# US_SB_Orinet.net
KiCad netlist of a schematic drawn in Altium Designer
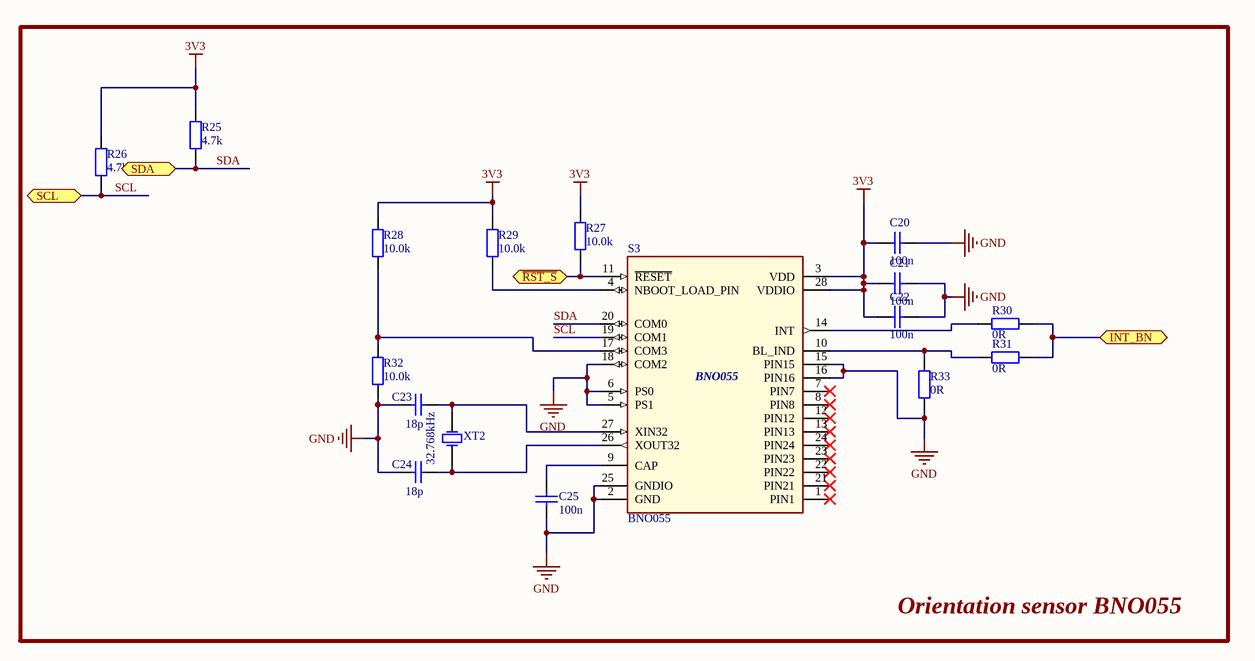
[diagram p0: US_SB_Orinet.SchDoc]

(export (version "E")
  (design (tool "Eeschema 10.0.6"))
  (components
    (comp (ref "C20")
      (value "100n")
      (footprint "C0603_IPC_HD")
      (description "CAP CER 0.1UF 16V X7R 0603")
      (fields
        (field (name "MANUFACTURER") "Samsung Electro-Mechanics")
        (field (name "MANUFACTURER PART NUMBER") "CL10B104KO8NNNC")
      )
      (libsource (lib "alfasat_parts_lib") (part "CL10B104KO8NNNC"))
    )
    (comp (ref "C21")
      (value "100n")
      (footprint "C0603_IPC_HD")
      (description "CAP CER 0.1UF 16V X7R 0603")
      (fields
        (field (name "MANUFACTURER") "Samsung Electro-Mechanics")
        (field (name "MANUFACTURER PART NUMBER") "CL10B104KO8NNNC")
      )
      (libsource (lib "alfasat_parts_lib") (part "CL10B104KO8NNNC"))
    )
    (comp (ref "C22")
      (value "100n")
      (footprint "C0603_IPC_HD")
      (description "CAP CER 0.1UF 16V X7R 0603")
      (fields
        (field (name "MANUFACTURER") "Samsung Electro-Mechanics")
        (field (name "MANUFACTURER PART NUMBER") "CL10B104KO8NNNC")
      )
      (libsource (lib "alfasat_parts_lib") (part "CL10B104KO8NNNC"))
    )
    (comp (ref "C23")
      (value "18p")
      (footprint "C0603_IPC_HD")
      (description "CAP CER 18PF 50V C0G/NP0 0603")
      (fields
        (field (name "MANUFACTURER") "Samsung Electro-Mechanics")
        (field (name "MANUFACTURER PART NUMBER") "CL10C180JB8NNNC")
      )
      (libsource (lib "alfasat_lib") (part "CL10C180JB8NNNC"))
    )
    (comp (ref "C24")
      (value "18p")
      (footprint "C0603_IPC_HD")
      (description "CAP CER 18PF 50V C0G/NP0 0603")
      (fields
        (field (name "MANUFACTURER") "Samsung Electro-Mechanics")
        (field (name "MANUFACTURER PART NUMBER") "CL10C180JB8NNNC")
      )
      (libsource (lib "alfasat_lib") (part "CL10C180JB8NNNC"))
    )
    (comp (ref "C25")
      (value "100n")
      (footprint "C0603_IPC_HD")
      (description "CAP CER 0.1UF 16V X7R 0603")
      (fields
        (field (name "MANUFACTURER") "Samsung Electro-Mechanics")
        (field (name "MANUFACTURER PART NUMBER") "CL10B104KO8NNNC")
      )
      (libsource (lib "alfasat_parts_lib") (part "CL10B104KO8NNNC"))
    )
    (comp (ref "R25")
      (value "4.7k")
      (footprint "R0603_IPC_HD")
      (description "RES SMD 4.7K OHM 5% 1/10W 0603")
      (fields
        (field (name "MANUFACTURER") "Bourns Inc.")
        (field (name "MANUFACTURER PART NUMBER") "CR0603-JW-472ELF")
      )
      (libsource (lib "alfasat_lib_eps") (part "CR0603-JW-4.7k"))
    )
    (comp (ref "R26")
      (value "4.7k")
      (footprint "R0603_IPC_HD")
      (description "RES SMD 4.7K OHM 5% 1/10W 0603")
      (fields
        (field (name "MANUFACTURER") "Bourns Inc.")
        (field (name "MANUFACTURER PART NUMBER") "CR0603-JW-472ELF")
      )
      (libsource (lib "alfasat_lib_eps") (part "CR0603-JW-4.7k"))
    )
    (comp (ref "R27")
      (value "10.0k")
      (footprint "R0603_IPC_MD")
      (description "RES 10K OHM 1% 1/10W 0603")
      (fields
        (field (name "MANUFACTURER") "Stackpole Electronics Inc")
        (field (name "MANUFACTURER PART NUMBER") "RMCF0603FT10K0")
      )
      (libsource (lib "alfasat_parts_lib") (part "RMCF0603FT10K0"))
    )
    (comp (ref "R28")
      (value "10.0k")
      (footprint "R0603_IPC_MD")
      (description "RES 10K OHM 1% 1/10W 0603")
      (fields
        (field (name "MANUFACTURER") "Stackpole Electronics Inc")
        (field (name "MANUFACTURER PART NUMBER") "RMCF0603FT10K0")
      )
      (libsource (lib "alfasat_parts_lib") (part "RMCF0603FT10K0"))
    )
    (comp (ref "R29")
      (value "10.0k")
      (footprint "R0603_IPC_MD")
      (description "RES 10K OHM 1% 1/10W 0603")
      (fields
        (field (name "MANUFACTURER") "Stackpole Electronics Inc")
        (field (name "MANUFACTURER PART NUMBER") "RMCF0603FT10K0")
      )
      (libsource (lib "alfasat_parts_lib") (part "RMCF0603FT10K0"))
    )
    (comp (ref "R30")
      (value "0R")
      (footprint "R0603_IPC_MD")
      (description "RES SMD 0 OHM JUMPER 1/10W 0603")
      (fields
        (field (name "MANUFACTURER") "Bourns Inc.")
        (field (name "MANUFACTURER PART NUMBER") "CR0603-J/-000ELF")
      )
      (libsource (lib "") (part "CR0603-J/-000ELF_1"))
    )
    (comp (ref "R31")
      (value "0R")
      (footprint "R0603_IPC_MD")
      (description "RES SMD 0 OHM JUMPER 1/10W 0603")
      (fields
        (field (name "MANUFACTURER") "Bourns Inc.")
        (field (name "MANUFACTURER PART NUMBER") "CR0603-J/-000ELF")
      )
      (libsource (lib "") (part "CR0603-J/-000ELF_1"))
    )
    (comp (ref "R32")
      (value "10.0k")
      (footprint "R0603_IPC_MD")
      (description "RES 10K OHM 1% 1/10W 0603")
      (fields
        (field (name "MANUFACTURER") "Stackpole Electronics Inc")
        (field (name "MANUFACTURER PART NUMBER") "RMCF0603FT10K0")
      )
      (libsource (lib "alfasat_parts_lib") (part "RMCF0603FT10K0"))
    )
    (comp (ref "R33")
      (value "0R")
      (footprint "R0603_IPC_MD")
      (description "RES SMD 0 OHM JUMPER 1/10W 0603")
      (fields
        (field (name "MANUFACTURER") "Bourns Inc.")
        (field (name "MANUFACTURER PART NUMBER") "CR0603-J/-000ELF")
      )
      (libsource (lib "alfasat_lib") (part "CR0603-J/-000ELF"))
    )
    (comp (ref "S3")
      (value "BNO055")
      (footprint "BNO055_LGA28R50P4X10_380X520X100")
      (description "Accelerometer, Gyroscope, Magnetometer, 3 Axis Sensor I²C, UART Output")
      (fields (field (name "MANUFACTURER") "Bosch Sensortec"))
      (libsource (lib "alfasat_lib_eps") (part "BNO055"))
    )
    (comp (ref "XT2")
      (value "32.768kHz")
      (footprint "FC-135R")
      (description "32.768kHz ±20ppm Crystal 12.5pF 70 kOhms 2-SMD, No Lead")
      (fields
        (field (name "MANUFACTURER") "EPSON")
        (field (name "MANUFACTURER PART NUMBER") "FC-135 32.7680KA-A5")
      )
      (libsource (lib "alfasat_lib_eps") (part "FC-135-32.7680K"))
    )
  )
  (nets
    (net (code "1") (name "/INT_BN") (class "Default")
      (node (ref "R30") (pin "1") (pinfunction "1_1") (pintype "passive"))
      (node (ref "R31") (pin "1") (pinfunction "1_1") (pintype "passive"))
    )
    (net (code "2") (name "/SCL") (class "Default")
      (node (ref "R26") (pin "1") (pinfunction "1_1") (pintype "passive"))
      (node (ref "S3") (pin "19") (pinfunction "COM1_19") (pintype "bidirectional"))
    )
    (net (code "3") (name "/SDA") (class "Default")
      (node (ref "R25") (pin "1") (pinfunction "1_1") (pintype "passive"))
      (node (ref "S3") (pin "20") (pinfunction "COM0_20") (pintype "bidirectional"))
    )
    (net (code "4") (name "/~{RST_S}") (class "Default")
      (node (ref "R27") (pin "1") (pinfunction "1_1") (pintype "passive"))
      (node (ref "S3") (pin "11") (pinfunction "~{RESET}_11") (pintype "input"))
    )
    (net (code "5") (name "3V3") (class "Default")
      (node (ref "C20") (pin "1") (pinfunction "1_1") (pintype "passive"))
      (node (ref "C21") (pin "1") (pinfunction "1_1") (pintype "passive"))
      (node (ref "C22") (pin "1") (pinfunction "1_1") (pintype "passive"))
      (node (ref "R25") (pin "2") (pinfunction "2_2") (pintype "passive"))
      (node (ref "R26") (pin "2") (pinfunction "2_2") (pintype "passive"))
      (node (ref "R27") (pin "2") (pinfunction "2_2") (pintype "passive"))
      (node (ref "R28") (pin "2") (pinfunction "2_2") (pintype "passive"))
      (node (ref "R29") (pin "2") (pinfunction "2_2") (pintype "passive"))
      (node (ref "S3") (pin "28") (pinfunction "VDDIO_28") (pintype "passive"))
      (node (ref "S3") (pin "3") (pinfunction "VDD_3") (pintype "passive"))
    )
    (net (code "6") (name "GND") (class "Default")
      (node (ref "C20") (pin "2") (pinfunction "2_2") (pintype "passive"))
      (node (ref "C21") (pin "2") (pinfunction "2_2") (pintype "passive"))
      (node (ref "C22") (pin "2") (pinfunction "2_2") (pintype "passive"))
      (node (ref "C23") (pin "1") (pinfunction "1_1") (pintype "passive"))
      (node (ref "C24") (pin "1") (pinfunction "1_1") (pintype "passive"))
      (node (ref "C25") (pin "1") (pinfunction "1_1") (pintype "passive"))
      (node (ref "R32") (pin "1") (pinfunction "1_1") (pintype "passive"))
      (node (ref "R33") (pin "1") (pinfunction "1_1") (pintype "passive"))
      (node (ref "S3") (pin "15") (pinfunction "PIN15_15") (pintype "passive"))
      (node (ref "S3") (pin "16") (pinfunction "PIN16_16") (pintype "passive"))
      (node (ref "S3") (pin "18") (pinfunction "COM2_18") (pintype "bidirectional"))
      (node (ref "S3") (pin "2") (pinfunction "GND_2") (pintype "passive"))
      (node (ref "S3") (pin "25") (pinfunction "GNDIO_25") (pintype "passive"))
      (node (ref "S3") (pin "5") (pinfunction "PS1_5") (pintype "input"))
      (node (ref "S3") (pin "6") (pinfunction "PS0_6") (pintype "input"))
    )
    (net (code "7") (name "Net-(S3-BL_IND)") (class "Default")
      (node (ref "R31") (pin "2") (pinfunction "2_2") (pintype "passive"))
      (node (ref "R33") (pin "2") (pinfunction "2_2") (pintype "passive"))
      (node (ref "S3") (pin "10") (pinfunction "BL_IND_10") (pintype "passive"))
    )
    (net (code "8") (name "Net-(S3-CAP)") (class "Default")
      (node (ref "C25") (pin "2") (pinfunction "2_2") (pintype "passive"))
      (node (ref "S3") (pin "9") (pinfunction "CAP_9") (pintype "passive"))
    )
    (net (code "9") (name "Net-(S3-COM3)") (class "Default")
      (node (ref "R28") (pin "1") (pinfunction "1_1") (pintype "passive"))
      (node (ref "R32") (pin "2") (pinfunction "2_2") (pintype "passive"))
      (node (ref "S3") (pin "17") (pinfunction "COM3_17") (pintype "bidirectional"))
    )
    (net (code "10") (name "Net-(S3-INT)") (class "Default")
      (node (ref "R30") (pin "2") (pinfunction "2_2") (pintype "passive"))
      (node (ref "S3") (pin "14") (pinfunction "INT_14") (pintype "output"))
    )
    (net (code "11") (name "Net-(S3-NBOOT_LOAD_PIN)") (class "Default")
      (node (ref "R29") (pin "1") (pinfunction "1_1") (pintype "passive"))
      (node (ref "S3") (pin "4") (pinfunction "NBOOT_LOAD_PIN_4") (pintype "bidirectional"))
    )
    (net (code "12") (name "Net-(S3-XIN32)") (class "Default")
      (node (ref "C23") (pin "2") (pinfunction "2_2") (pintype "passive"))
      (node (ref "S3") (pin "27") (pinfunction "XIN32_27") (pintype "input"))
      (node (ref "XT2") (pin "2") (pinfunction "OSC2_2") (pintype "passive"))
    )
    (net (code "13") (name "Net-(S3-XOUT32)") (class "Default")
      (node (ref "C24") (pin "2") (pinfunction "2_2") (pintype "passive"))
      (node (ref "S3") (pin "26") (pinfunction "XOUT32_26") (pintype "output"))
      (node (ref "XT2") (pin "1") (pinfunction "OSC1_1") (pintype "passive"))
    )
    (net (code "14") (name "unconnected-(S3-PIN1-Pad1)") (class "Default")
      (node (ref "S3") (pin "1") (pinfunction "PIN1_1") (pintype "passive+no_connect"))
    )
    (net (code "15") (name "unconnected-(S3-PIN7-Pad7)") (class "Default")
      (node (ref "S3") (pin "7") (pinfunction "PIN7_7") (pintype "passive+no_connect"))
    )
    (net (code "16") (name "unconnected-(S3-PIN8-Pad8)") (class "Default")
      (node (ref "S3") (pin "8") (pinfunction "PIN8_8") (pintype "passive+no_connect"))
    )
    (net (code "17") (name "unconnected-(S3-PIN12-Pad12)") (class "Default")
      (node (ref "S3") (pin "12") (pinfunction "PIN12_12") (pintype "passive+no_connect"))
    )
    (net (code "18") (name "unconnected-(S3-PIN13-Pad13)") (class "Default")
      (node (ref "S3") (pin "13") (pinfunction "PIN13_13") (pintype "passive+no_connect"))
    )
    (net (code "19") (name "unconnected-(S3-PIN21-Pad21)") (class "Default")
      (node (ref "S3") (pin "21") (pinfunction "PIN21_21") (pintype "passive+no_connect"))
    )
    (net (code "20") (name "unconnected-(S3-PIN22-Pad22)") (class "Default")
      (node (ref "S3") (pin "22") (pinfunction "PIN22_22") (pintype "passive+no_connect"))
    )
    (net (code "21") (name "unconnected-(S3-PIN23-Pad23)") (class "Default")
      (node (ref "S3") (pin "23") (pinfunction "PIN23_23") (pintype "passive+no_connect"))
    )
    (net (code "22") (name "unconnected-(S3-PIN24-Pad24)") (class "Default")
      (node (ref "S3") (pin "24") (pinfunction "PIN24_24") (pintype "passive+no_connect"))
    )
  )
)
